# DAC.net
KiCad netlist of a schematic drawn in Altium Designer
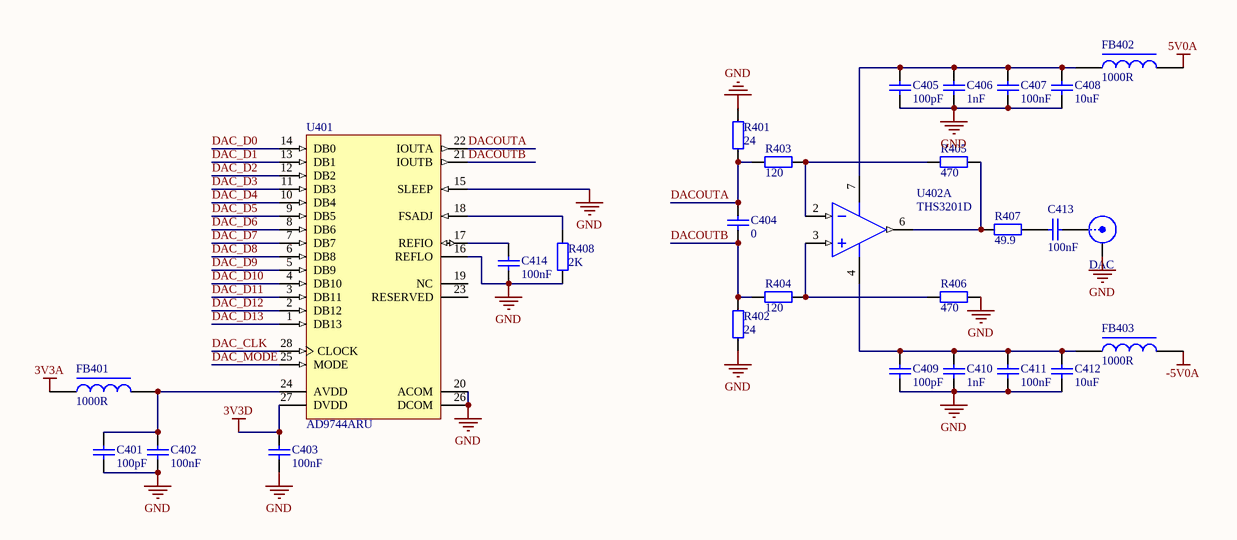
[diagram p0: DAC.SchDoc]

(export (version "E")
  (design (tool "Eeschema 10.0.6"))
  (components
    (comp (ref "C401")
      (value "100pF")
      (footprint "0402C")
      (description "MLCC")
      (libsource (lib "Misc") (part "MLCC"))
    )
    (comp (ref "C402")
      (value "100nF")
      (footprint "0402C")
      (description "MLCC")
      (libsource (lib "Misc") (part "MLCC"))
    )
    (comp (ref "C403")
      (value "100nF")
      (footprint "0402C")
      (description "MLCC")
      (libsource (lib "Misc") (part "MLCC"))
    )
    (comp (ref "C404")
      (value "0")
      (footprint "0603C")
      (description "MLCC")
      (libsource (lib "Misc") (part "MLCC"))
    )
    (comp (ref "C405")
      (value "100pF")
      (footprint "0402C")
      (description "MLCC")
      (libsource (lib "Misc") (part "MLCC"))
    )
    (comp (ref "C406")
      (value "1nF")
      (footprint "0402C")
      (description "MLCC")
      (libsource (lib "Misc") (part "MLCC"))
    )
    (comp (ref "C407")
      (value "100nF")
      (footprint "0603C")
      (description "MLCC")
      (libsource (lib "Misc") (part "MLCC"))
    )
    (comp (ref "C408")
      (value "10uF")
      (footprint "0805C")
      (description "MLCC")
      (libsource (lib "Misc") (part "MLCC"))
    )
    (comp (ref "C409")
      (value "100pF")
      (footprint "0402C")
      (description "MLCC")
      (libsource (lib "Misc") (part "MLCC"))
    )
    (comp (ref "C410")
      (value "1nF")
      (footprint "0402C")
      (description "MLCC")
      (libsource (lib "Misc") (part "MLCC"))
    )
    (comp (ref "C411")
      (value "100nF")
      (footprint "0603C")
      (description "MLCC")
      (libsource (lib "Misc") (part "MLCC"))
    )
    (comp (ref "C412")
      (value "10uF")
      (footprint "0805C")
      (description "MLCC")
      (libsource (lib "Misc") (part "MLCC"))
    )
    (comp (ref "C413")
      (value "100nF")
      (footprint "0603C")
      (description "MLCC")
      (libsource (lib "Misc") (part "MLCC"))
    )
    (comp (ref "C414")
      (value "100nF")
      (footprint "0402C")
      (description "MLCC")
      (libsource (lib "Misc") (part "MLCC"))
    )
    (comp (ref "DAC")
      (value "SMA")
      (footprint "SMA-V")
      (description "SMA Connector")
      (libsource (lib "SMA") (part "SMA"))
    )
    (comp (ref "FB401")
      (value "1000R")
      (footprint "0603L")
      (description "FerriteBead")
      (libsource (lib "Misc") (part "FerriteBead"))
    )
    (comp (ref "FB402")
      (value "1000R")
      (footprint "0603L")
      (description "FerriteBead")
      (libsource (lib "Misc") (part "FerriteBead"))
    )
    (comp (ref "FB403")
      (value "1000R")
      (footprint "0603L")
      (description "FerriteBead")
      (libsource (lib "Misc") (part "FerriteBead"))
    )
    (comp (ref "R401")
      (value "24")
      (footprint "0603R")
      (description "Resistor")
      (libsource (lib "Misc") (part "Resistor"))
    )
    (comp (ref "R402")
      (value "24")
      (footprint "0603R")
      (description "Resistor")
      (libsource (lib "Misc") (part "Resistor"))
    )
    (comp (ref "R403")
      (value "120")
      (footprint "0603R")
      (description "Resistor")
      (libsource (lib "") (part "Resistor_1"))
    )
    (comp (ref "R404")
      (value "120")
      (footprint "0603R")
      (description "Resistor")
      (libsource (lib "") (part "Resistor_1"))
    )
    (comp (ref "R405")
      (value "470")
      (footprint "0603R")
      (description "Resistor")
      (libsource (lib "") (part "Resistor_1"))
    )
    (comp (ref "R406")
      (value "470")
      (footprint "0603R")
      (description "Resistor")
      (libsource (lib "") (part "Resistor_1"))
    )
    (comp (ref "R407")
      (value "49.9")
      (footprint "0603R")
      (description "Resistor")
      (libsource (lib "") (part "Resistor_1"))
    )
    (comp (ref "R408")
      (value "2K")
      (footprint "0603R")
      (description "Resistor")
      (libsource (lib "Misc") (part "Resistor"))
    )
    (comp (ref "U401")
      (value "AD9744ARU")
      (footprint "RU-28_N")
      (description "Single 14-Bit TxDAC, 210 Msps, -40 to +85 degC, RU-28, Tube")
      (fields (field (name "GENERIC PART NUMBER") "AD9744") (field (name "MANUFACTURER") "Analog Devices"))
      (libsource (lib "Analog Devices Data Converters Digital-to-Analog Converters") (part "AD9744ARU"))
    )
    (comp (ref "U402")
      (value "THS3201D")
      (footprint "D0008A_N")
      (fields (field (name "MANUFACTURER") "Texas Instruments"))
      (libsource (lib "Altium Content Vault") (part "CMP-0018-00113-2"))
    )
  )
  (nets
    (net (code "1") (name "-5V0A") (class "Default")
      (node (ref "FB403") (pin "2") (pinfunction "2_2") (pintype "passive"))
    )
    (net (code "2") (name "/DACOUTA") (class "Default")
      (node (ref "C404") (pin "2") (pinfunction "2_2") (pintype "passive"))
      (node (ref "R401") (pin "1") (pinfunction "1_1") (pintype "passive"))
      (node (ref "R403") (pin "1") (pinfunction "1_1") (pintype "passive"))
      (node (ref "U401") (pin "22") (pinfunction "IOUTA_22") (pintype "output"))
    )
    (net (code "3") (name "/DACOUTB") (class "Default")
      (node (ref "C404") (pin "1") (pinfunction "1_1") (pintype "passive"))
      (node (ref "R402") (pin "2") (pinfunction "2_2") (pintype "passive"))
      (node (ref "R404") (pin "1") (pinfunction "1_1") (pintype "passive"))
      (node (ref "U401") (pin "21") (pinfunction "IOUTB_21") (pintype "output"))
    )
    (net (code "4") (name "/DAC_CLK") (class "Default")
      (node (ref "U401") (pin "28") (pinfunction "CLOCK_28") (pintype "input"))
    )
    (net (code "5") (name "/DAC_D0") (class "Default")
      (node (ref "U401") (pin "14") (pinfunction "DB0_14") (pintype "input"))
    )
    (net (code "6") (name "/DAC_D1") (class "Default")
      (node (ref "U401") (pin "13") (pinfunction "DB1_13") (pintype "input"))
    )
    (net (code "7") (name "/DAC_D2") (class "Default")
      (node (ref "U401") (pin "12") (pinfunction "DB2_12") (pintype "input"))
    )
    (net (code "8") (name "/DAC_D3") (class "Default")
      (node (ref "U401") (pin "11") (pinfunction "DB3_11") (pintype "input"))
    )
    (net (code "9") (name "/DAC_D4") (class "Default")
      (node (ref "U401") (pin "10") (pinfunction "DB4_10") (pintype "input"))
    )
    (net (code "10") (name "/DAC_D5") (class "Default")
      (node (ref "U401") (pin "9") (pinfunction "DB5_9") (pintype "input"))
    )
    (net (code "11") (name "/DAC_D6") (class "Default")
      (node (ref "U401") (pin "8") (pinfunction "DB6_8") (pintype "input"))
    )
    (net (code "12") (name "/DAC_D7") (class "Default")
      (node (ref "U401") (pin "7") (pinfunction "DB7_7") (pintype "input"))
    )
    (net (code "13") (name "/DAC_D8") (class "Default")
      (node (ref "U401") (pin "6") (pinfunction "DB8_6") (pintype "input"))
    )
    (net (code "14") (name "/DAC_D9") (class "Default")
      (node (ref "U401") (pin "5") (pinfunction "DB9_5") (pintype "input"))
    )
    (net (code "15") (name "/DAC_D10") (class "Default")
      (node (ref "U401") (pin "4") (pinfunction "DB10_4") (pintype "input"))
    )
    (net (code "16") (name "/DAC_D11") (class "Default")
      (node (ref "U401") (pin "3") (pinfunction "DB11_3") (pintype "input"))
    )
    (net (code "17") (name "/DAC_D12") (class "Default")
      (node (ref "U401") (pin "2") (pinfunction "DB12_2") (pintype "input"))
    )
    (net (code "18") (name "/DAC_D13") (class "Default")
      (node (ref "U401") (pin "1") (pinfunction "DB13_1") (pintype "input"))
    )
    (net (code "19") (name "/DAC_MODE") (class "Default")
      (node (ref "U401") (pin "25") (pinfunction "MODE_25") (pintype "input"))
    )
    (net (code "20") (name "3V3A") (class "Default")
      (node (ref "FB401") (pin "1") (pinfunction "1_1") (pintype "passive"))
    )
    (net (code "21") (name "3V3D") (class "Default")
      (node (ref "C403") (pin "2") (pinfunction "2_2") (pintype "passive"))
      (node (ref "U401") (pin "27") (pinfunction "DVDD_27") (pintype "power_in"))
    )
    (net (code "22") (name "5V0A") (class "Default")
      (node (ref "FB402") (pin "2") (pinfunction "2_2") (pintype "passive"))
    )
    (net (code "23") (name "GND") (class "Default")
      (node (ref "C401") (pin "1") (pinfunction "1_1") (pintype "passive"))
      (node (ref "C402") (pin "1") (pinfunction "1_1") (pintype "passive"))
      (node (ref "C403") (pin "1") (pinfunction "1_1") (pintype "passive"))
      (node (ref "C405") (pin "1") (pinfunction "1_1") (pintype "passive"))
      (node (ref "C406") (pin "1") (pinfunction "1_1") (pintype "passive"))
      (node (ref "C407") (pin "1") (pinfunction "1_1") (pintype "passive"))
      (node (ref "C408") (pin "1") (pinfunction "1_1") (pintype "passive"))
      (node (ref "C409") (pin "1") (pinfunction "1_1") (pintype "passive"))
      (node (ref "C410") (pin "1") (pinfunction "1_1") (pintype "passive"))
      (node (ref "C411") (pin "1") (pinfunction "1_1") (pintype "passive"))
      (node (ref "C412") (pin "1") (pinfunction "1_1") (pintype "passive"))
      (node (ref "C414") (pin "1") (pinfunction "1_1") (pintype "passive"))
      (node (ref "DAC") (pin "2") (pinfunction "Y_2") (pintype "passive"))
      (node (ref "R401") (pin "2") (pinfunction "2_2") (pintype "passive"))
      (node (ref "R402") (pin "1") (pinfunction "1_1") (pintype "passive"))
      (node (ref "R406") (pin "2") (pinfunction "2_2") (pintype "passive"))
      (node (ref "R408") (pin "1") (pinfunction "1_1") (pintype "passive"))
      (node (ref "U401") (pin "15") (pinfunction "SLEEP_15") (pintype "input"))
      (node (ref "U401") (pin "16") (pinfunction "REFLO_16") (pintype "passive"))
      (node (ref "U401") (pin "20") (pinfunction "ACOM_20") (pintype "power_in"))
      (node (ref "U401") (pin "26") (pinfunction "DCOM_26") (pintype "power_in"))
    )
    (net (code "24") (name "Net-(C413-Pad1)") (class "Default")
      (node (ref "C413") (pin "1") (pinfunction "1_1") (pintype "passive"))
      (node (ref "R407") (pin "2") (pinfunction "2_2") (pintype "passive"))
    )
    (net (code "25") (name "Net-(DAC-X)") (class "Default")
      (node (ref "C413") (pin "2") (pinfunction "2_2") (pintype "passive"))
      (node (ref "DAC") (pin "1") (pinfunction "X_1") (pintype "passive"))
    )
    (net (code "26") (name "Net-(U401-AVDD)") (class "Default")
      (node (ref "C401") (pin "2") (pinfunction "2_2") (pintype "passive"))
      (node (ref "C402") (pin "2") (pinfunction "2_2") (pintype "passive"))
      (node (ref "FB401") (pin "2") (pinfunction "2_2") (pintype "passive"))
      (node (ref "U401") (pin "24") (pinfunction "AVDD_24") (pintype "power_in"))
    )
    (net (code "27") (name "Net-(U401-FSADJ)") (class "Default")
      (node (ref "R408") (pin "2") (pinfunction "2_2") (pintype "passive"))
      (node (ref "U401") (pin "18") (pinfunction "FSADJ_18") (pintype "input"))
    )
    (net (code "28") (name "Net-(U401-REFIO)") (class "Default")
      (node (ref "C414") (pin "2") (pinfunction "2_2") (pintype "passive"))
      (node (ref "U401") (pin "17") (pinfunction "REFIO_17") (pintype "bidirectional"))
    )
    (net (code "29") (name "Net-(U402A-VIN+)") (class "Default")
      (node (ref "R404") (pin "2") (pinfunction "2_2") (pintype "passive"))
      (node (ref "R406") (pin "1") (pinfunction "1_1") (pintype "passive"))
      (node (ref "U402") (pin "3") (pinfunction "VIN+_3") (pintype "input"))
    )
    (net (code "30") (name "Net-(U402A-VIN-)") (class "Default")
      (node (ref "R403") (pin "2") (pinfunction "2_2") (pintype "passive"))
      (node (ref "R405") (pin "1") (pinfunction "1_1") (pintype "passive"))
      (node (ref "U402") (pin "2") (pinfunction "VIN-_2") (pintype "input"))
    )
    (net (code "31") (name "Net-(U402A-VOUT)") (class "Default")
      (node (ref "R405") (pin "2") (pinfunction "2_2") (pintype "passive"))
      (node (ref "R407") (pin "1") (pinfunction "1_1") (pintype "passive"))
      (node (ref "U402") (pin "6") (pinfunction "VOUT_6") (pintype "output"))
    )
    (net (code "32") (name "Net-(U402A-VS+)") (class "Default")
      (node (ref "C405") (pin "2") (pinfunction "2_2") (pintype "passive"))
      (node (ref "C406") (pin "2") (pinfunction "2_2") (pintype "passive"))
      (node (ref "C407") (pin "2") (pinfunction "2_2") (pintype "passive"))
      (node (ref "C408") (pin "2") (pinfunction "2_2") (pintype "passive"))
      (node (ref "FB402") (pin "1") (pinfunction "1_1") (pintype "passive"))
      (node (ref "U402") (pin "7") (pinfunction "VS+_7") (pintype "power_in"))
    )
    (net (code "33") (name "Net-(U402A-VS-)") (class "Default")
      (node (ref "C409") (pin "2") (pinfunction "2_2") (pintype "passive"))
      (node (ref "C410") (pin "2") (pinfunction "2_2") (pintype "passive"))
      (node (ref "C411") (pin "2") (pinfunction "2_2") (pintype "passive"))
      (node (ref "C412") (pin "2") (pinfunction "2_2") (pintype "passive"))
      (node (ref "FB403") (pin "1") (pinfunction "1_1") (pintype "passive"))
      (node (ref "U402") (pin "4") (pinfunction "VS-_4") (pintype "power_in"))
    )
    (net (code "34") (name "unconnected-(U401-NC-Pad19)") (class "Default")
      (node (ref "U401") (pin "19") (pinfunction "NC_19") (pintype "passive"))
    )
    (net (code "35") (name "unconnected-(U401-RESERVED-Pad23)") (class "Default")
      (node (ref "U401") (pin "23") (pinfunction "RESERVED_23") (pintype "passive"))
    )
  )
)
